# CH32H417MEU6-UHSIF-Top-R0.net
KiCad netlist of a schematic drawn in Altium Designer
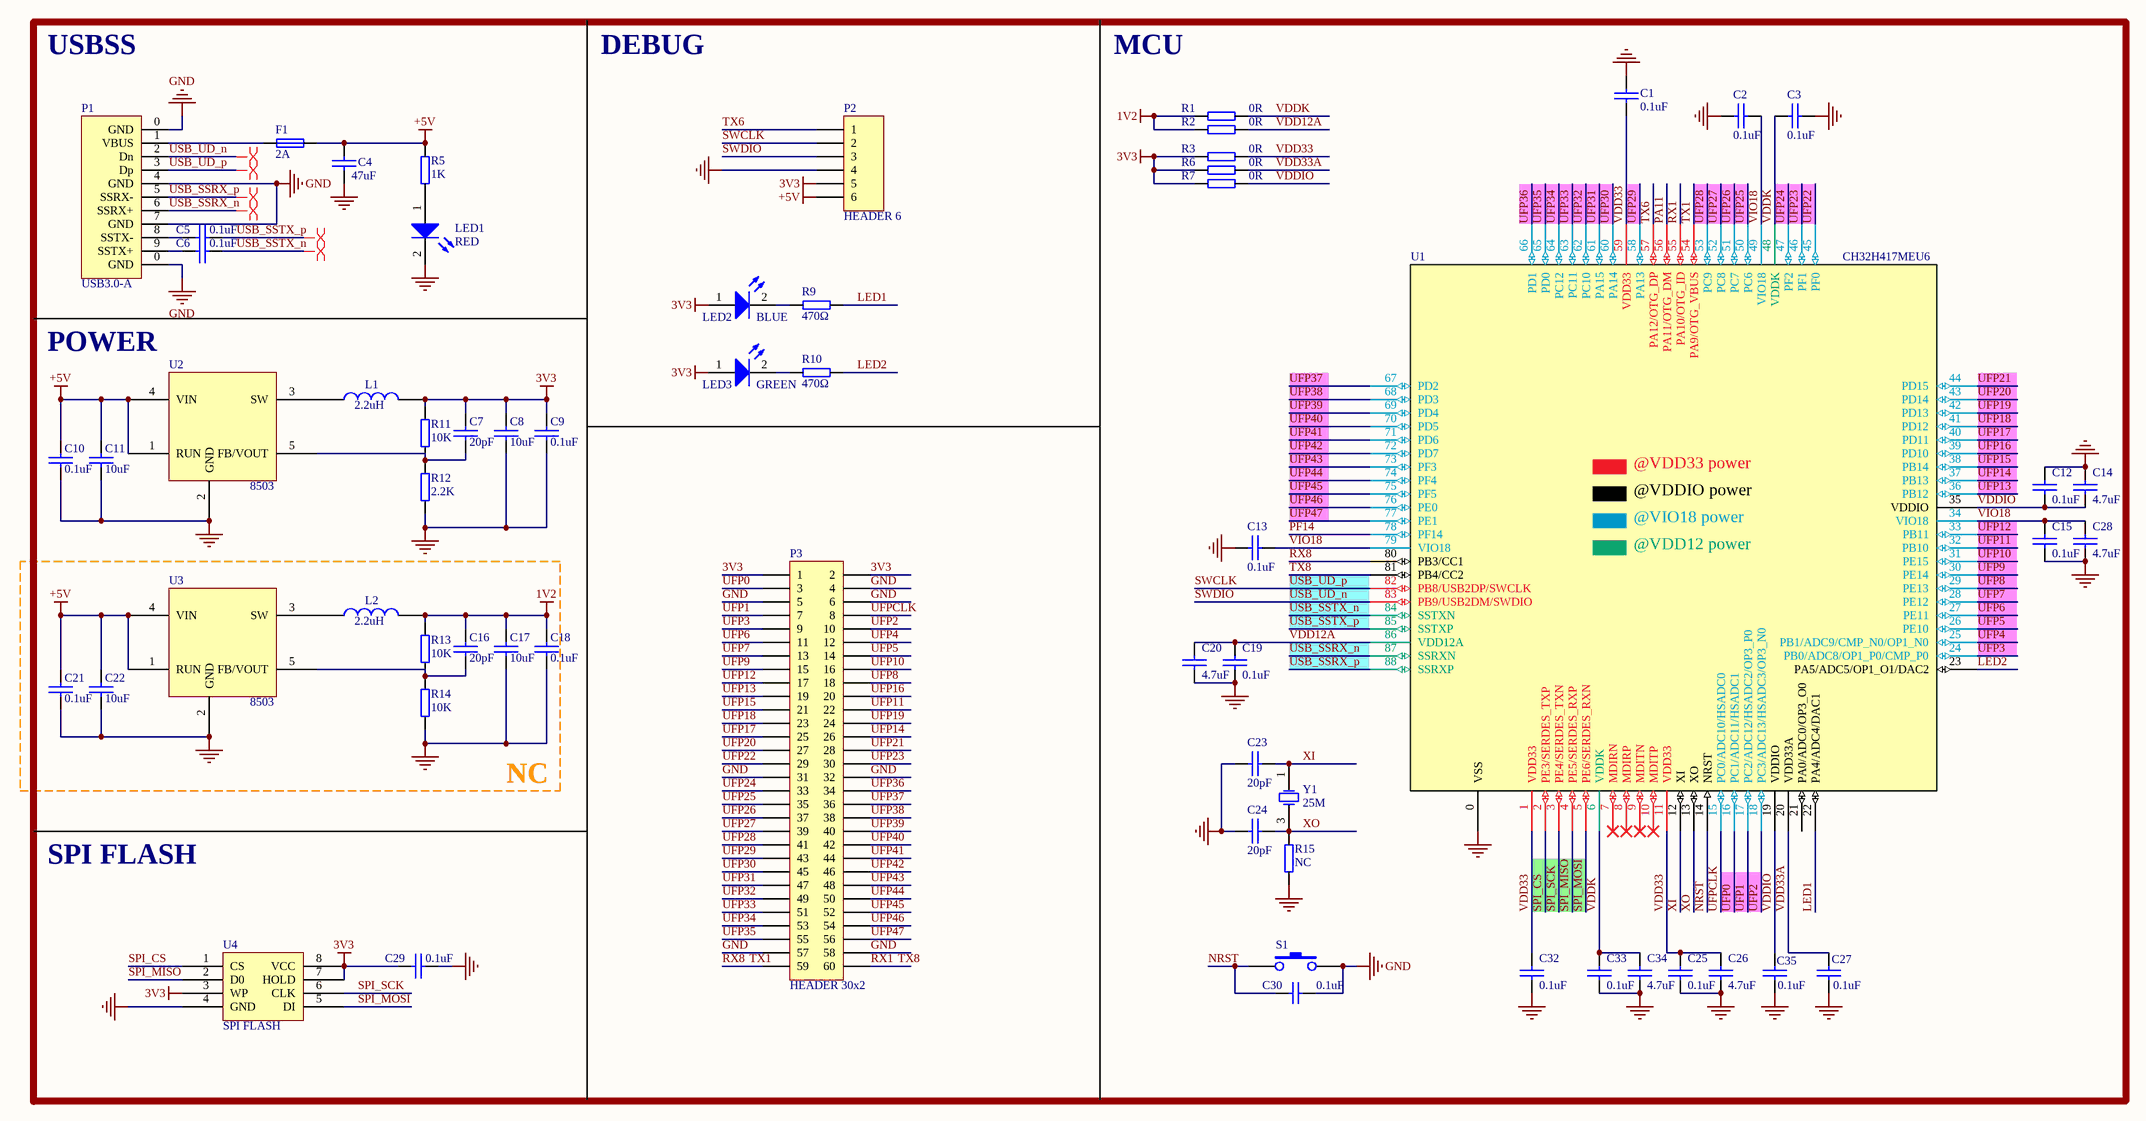
[diagram p0: CH32H417MEU6-UHSIF-Top-R0.SchDoc]

(export (version "E")
  (design (tool "Eeschema 10.0.6"))
  (components
    (comp (ref "C1")
      (value "0.1uF")
      (footprint "0402_C")
      (description "Capacitor")
      (libsource (lib "wch_sch_others") (part "CAP"))
    )
    (comp (ref "C2")
      (value "0.1uF")
      (footprint "0402_C")
      (description "Capacitor")
      (libsource (lib "wch_sch_others") (part "CAP"))
    )
    (comp (ref "C3")
      (value "0.1uF")
      (footprint "0402_C")
      (description "Capacitor")
      (libsource (lib "wch_sch_others") (part "CAP"))
    )
    (comp (ref "C4")
      (value "47uF")
      (footprint "3528_C")
      (description "Capacitor")
      (libsource (lib "wch_sch_others") (part "CAP"))
    )
    (comp (ref "C5")
      (value "0.1uF")
      (footprint "0402_C")
      (description "Capacitor")
      (libsource (lib "wch_sch_others") (part "CAP"))
    )
    (comp (ref "C6")
      (value "0.1uF")
      (footprint "0402_C")
      (description "Capacitor")
      (libsource (lib "wch_sch_others") (part "CAP"))
    )
    (comp (ref "C7")
      (value "20pF")
      (footprint "0402_C")
      (description "Capacitor")
      (libsource (lib "*") (part "CAP"))
    )
    (comp (ref "C8")
      (value "10uF")
      (footprint "0603_C")
      (description "Capacitor")
      (libsource (lib "") (part "CAP_1"))
    )
    (comp (ref "C9")
      (value "0.1uF")
      (footprint "0402_C")
      (description "Capacitor")
      (libsource (lib "*") (part "CAP"))
    )
    (comp (ref "C10")
      (value "0.1uF")
      (footprint "0402_C")
      (description "Capacitor")
      (libsource (lib "*") (part "CAP"))
    )
    (comp (ref "C11")
      (value "10uF")
      (footprint "0603_C")
      (description "Capacitor")
      (libsource (lib "") (part "CAP_1"))
    )
    (comp (ref "C12")
      (value "0.1uF")
      (footprint "0402_C")
      (description "Capacitor")
      (libsource (lib "wch_sch_others") (part "CAP"))
    )
    (comp (ref "C13")
      (value "0.1uF")
      (footprint "0402_C")
      (description "Capacitor")
      (libsource (lib "wch_sch_others") (part "CAP"))
    )
    (comp (ref "C14")
      (value "4.7uF")
      (footprint "0402_C")
      (description "Capacitor")
      (libsource (lib "wch_sch_others") (part "CAP"))
    )
    (comp (ref "C15")
      (value "0.1uF")
      (footprint "0402_C")
      (description "Capacitor")
      (libsource (lib "wch_sch_others") (part "CAP"))
    )
    (comp (ref "C16")
      (value "20pF")
      (footprint "0402_C")
      (description "Capacitor")
      (libsource (lib "*") (part "CAP"))
    )
    (comp (ref "C17")
      (value "10uF")
      (footprint "0603_C")
      (description "Capacitor")
      (libsource (lib "") (part "CAP_1"))
    )
    (comp (ref "C18")
      (value "0.1uF")
      (footprint "0402_C")
      (description "Capacitor")
      (libsource (lib "*") (part "CAP"))
    )
    (comp (ref "C19")
      (value "0.1uF")
      (footprint "0402_C")
      (description "Capacitor")
      (libsource (lib "wch_sch_others") (part "CAP"))
    )
    (comp (ref "C20")
      (value "4.7uF")
      (footprint "0402_C")
      (description "Capacitor")
      (libsource (lib "wch_sch_others") (part "CAP"))
    )
    (comp (ref "C21")
      (value "0.1uF")
      (footprint "0402_C")
      (description "Capacitor")
      (libsource (lib "*") (part "CAP"))
    )
    (comp (ref "C22")
      (value "10uF")
      (footprint "0603_C")
      (description "Capacitor")
      (libsource (lib "") (part "CAP_1"))
    )
    (comp (ref "C23")
      (value "20pF")
      (footprint "0402_C")
      (description "Capacitor")
      (libsource (lib "wch_sch_others") (part "CAP"))
    )
    (comp (ref "C24")
      (value "20pF")
      (footprint "0402_C")
      (description "Capacitor")
      (libsource (lib "wch_sch_others") (part "CAP"))
    )
    (comp (ref "C25")
      (value "0.1uF")
      (footprint "0402_C")
      (description "Capacitor")
      (libsource (lib "wch_sch_others") (part "CAP"))
    )
    (comp (ref "C26")
      (value "4.7uF")
      (footprint "0402_C")
      (description "Capacitor")
      (libsource (lib "wch_sch_others") (part "CAP"))
    )
    (comp (ref "C27")
      (value "0.1uF")
      (footprint "0402_C")
      (description "Capacitor")
      (libsource (lib "wch_sch_others") (part "CAP"))
    )
    (comp (ref "C28")
      (value "4.7uF")
      (footprint "0402_C")
      (description "Capacitor")
      (libsource (lib "wch_sch_others") (part "CAP"))
    )
    (comp (ref "C29")
      (value "0.1uF")
      (footprint "0402_C")
      (description "Capacitor")
      (libsource (lib "wch_sch_others") (part "CAP"))
    )
    (comp (ref "C30")
      (value "0.1uF")
      (footprint "0402_C")
      (description "Capacitor")
      (libsource (lib "Miscellaneous Devices") (part "Cap"))
    )
    (comp (ref "C32")
      (value "0.1uF")
      (footprint "0402_C")
      (description "Capacitor")
      (libsource (lib "wch_sch_others") (part "CAP"))
    )
    (comp (ref "C33")
      (value "0.1uF")
      (footprint "0402_C")
      (description "Capacitor")
      (libsource (lib "wch_sch_others") (part "CAP"))
    )
    (comp (ref "C34")
      (value "4.7uF")
      (footprint "0402_C")
      (description "Capacitor")
      (libsource (lib "wch_sch_others") (part "CAP"))
    )
    (comp (ref "C35")
      (value "0.1uF")
      (footprint "0402_C")
      (description "Capacitor")
      (libsource (lib "wch_sch_others") (part "CAP"))
    )
    (comp (ref "F1")
      (value "2A")
      (footprint "0805")
      (description "Fuse")
      (libsource (lib "wch_sch_others") (part "FUSE1"))
    )
    (comp (ref "L1") (value "2.2uH") (footprint "CD32") (libsource (lib "*") (part "INDUCTOR")))
    (comp (ref "L2") (value "2.2uH") (footprint "CD32") (libsource (lib "*") (part "INDUCTOR")))
    (comp (ref "LED1")
      (value "RED")
      (footprint "MYPCB:0603+")
      (description "Typical INFRARED GaAs LED")
      (libsource (lib "wch_sch_others") (part "LED"))
    )
    (comp (ref "LED2")
      (value "BLUE")
      (footprint "MYPCB:0603+")
      (description "Typical INFRARED GaAs LED")
      (libsource (lib "wch_sch_others") (part "LED"))
    )
    (comp (ref "LED3")
      (value "GREEN")
      (footprint "MYPCB:0603+")
      (description "Typical INFRARED GaAs LED")
      (libsource (lib "wch_sch_others") (part "LED"))
    )
    (comp (ref "P1")
      (value "USB3.0-A")
      (footprint "USB3.0-A-Receptacle")
      (libsource (lib "wch_sch_others") (part "USB3.0-A"))
    )
    (comp (ref "P2")
      (value "HEADER 6")
      (footprint "SIP6-2.54mm")
      (description "Header, 6-Pin")
      (libsource (lib "wch_sch_others") (part "HEADER 6"))
    )
    (comp (ref "P3")
      (value "HEADER 30x2")
      (footprint "MYPCB:BTB-60P-P0.5-FR")
      (description "Header, 30-Pin, Dual row")
      (libsource (lib "wch_sch_others") (part "HEADER 30x2"))
    )
    (comp (ref "R1") (value "0R") (footprint "0603") (libsource (lib "wch_sch_others") (part "RES")))
    (comp (ref "R2") (value "0R") (footprint "0603") (libsource (lib "wch_sch_others") (part "RES")))
    (comp (ref "R3") (value "0R") (footprint "0603") (libsource (lib "wch_sch_others") (part "RES")))
    (comp (ref "R5") (value "1K") (footprint "0402") (libsource (lib "wch_sch_others") (part "RES")))
    (comp (ref "R6") (value "0R") (footprint "0603") (libsource (lib "wch_sch_others") (part "RES")))
    (comp (ref "R7") (value "0R") (footprint "0603") (libsource (lib "wch_sch_others") (part "RES")))
    (comp (ref "R9") (value "470Ω") (footprint "0402") (libsource (lib "wch_sch_others") (part "RES")))
    (comp (ref "R10") (value "470Ω") (footprint "0402") (libsource (lib "wch_sch_others") (part "RES")))
    (comp (ref "R11") (value "10K") (footprint "0402") (libsource (lib "*") (part "R")))
    (comp (ref "R12") (value "2.2K") (footprint "0402") (libsource (lib "*") (part "R")))
    (comp (ref "R13") (value "10K") (footprint "0402") (libsource (lib "*") (part "R")))
    (comp (ref "R14") (value "10K") (footprint "0402") (libsource (lib "*") (part "R")))
    (comp (ref "R15") (value "NC") (footprint "0402") (libsource (lib "*") (part "RES")))
    (comp (ref "S1") (value "~") (footprint "贴片按键") (libsource (lib "wch_sch_others") (part "KEY1")))
    (comp (ref "U1")
      (value "CH32H417MEU6")
      (footprint "QFN88_10X10")
      (description "RISC-V FPU HD-MCU, 384MHz, USB3.0 & PD, 100M Ethernet, DVP, SDMMC, QSPI, OPA, ADC, DAC")
      (libsource (lib "DHXXXSCH") (part "CH32H417MEU6"))
    )
    (comp (ref "U2") (value "8503") (footprint "SOT-23-5") (libsource (lib "*") (part "FP6160")))
    (comp (ref "U3") (value "8503") (footprint "SOT-23-5") (libsource (lib "*") (part "FP6160")))
    (comp (ref "U4")
      (value "SPI FLASH")
      (footprint "SOIC-8_208mil")
      (libsource (lib "wch_sch_others") (part "W25Q64"))
    )
    (comp (ref "Y1")
      (value "25M")
      (footprint "XT3225")
      (description "Crystal Oscillator")
      (fields (field (name "PUBLISHER") "Altium Limited"))
      (libsource (lib "Miscellaneous Devices") (part "XTAL"))
    )
  )
  (nets
    (net (code "1") (name "+5V") (class "Default")
      (node (ref "C10") (pin "2") (pinfunction "2_2") (pintype "passive"))
      (node (ref "C11") (pin "2") (pinfunction "2_2") (pintype "passive"))
      (node (ref "C21") (pin "2") (pinfunction "2_2") (pintype "passive"))
      (node (ref "C22") (pin "2") (pinfunction "2_2") (pintype "passive"))
      (node (ref "C4") (pin "1") (pinfunction "1_1") (pintype "passive"))
      (node (ref "F1") (pin "2") (pintype "passive"))
      (node (ref "P2") (pin "6") (pinfunction "6_6") (pintype "passive"))
      (node (ref "R5") (pin "2") (pintype "passive"))
      (node (ref "U2") (pin "1") (pinfunction "RUN_1") (pintype "passive"))
      (node (ref "U2") (pin "4") (pinfunction "VIN_4") (pintype "passive"))
      (node (ref "U3") (pin "1") (pinfunction "RUN_1") (pintype "passive"))
      (node (ref "U3") (pin "4") (pinfunction "VIN_4") (pintype "passive"))
    )
    (net (code "2") (name "/LED1") (class "Default")
      (node (ref "R9") (pin "1") (pintype "passive"))
      (node (ref "U1") (pin "22") (pinfunction "PA4/ADC4/DAC1_22") (pintype "bidirectional"))
    )
    (net (code "3") (name "/LED2") (class "Default")
      (node (ref "R10") (pin "1") (pintype "passive"))
      (node (ref "U1") (pin "23") (pinfunction "PA5/ADC5/OP1_O1/DAC2_23") (pintype "bidirectional"))
    )
    (net (code "4") (name "/NRST") (class "Default")
      (node (ref "C30") (pin "2") (pinfunction "2_2") (pintype "passive"))
      (node (ref "S1") (pin "1") (pinfunction "1_1") (pintype "passive"))
      (node (ref "U1") (pin "14") (pinfunction "NRST_14") (pintype "input"))
    )
    (net (code "5") (name "/PA11") (class "Default")
      (node (ref "U1") (pin "56") (pinfunction "PA11/OTG_DM_56") (pintype "bidirectional"))
    )
    (net (code "6") (name "/PF14") (class "Default")
      (node (ref "U1") (pin "78") (pinfunction "PF14_78") (pintype "bidirectional"))
    )
    (net (code "7") (name "/RX1") (class "Default")
      (node (ref "P3") (pin "60") (pinfunction "60_60") (pintype "passive"))
      (node (ref "U1") (pin "55") (pinfunction "PA10/OTG_ID_55") (pintype "bidirectional"))
      (node (ref "U1") (pin "81") (pinfunction "PB4/CC2_81") (pintype "bidirectional"))
    )
    (net (code "8") (name "/RX8") (class "Default")
      (node (ref "P3") (pin "59") (pinfunction "59_59") (pintype "passive"))
      (node (ref "U1") (pin "54") (pinfunction "PA9/OTG_VBUS_54") (pintype "bidirectional"))
      (node (ref "U1") (pin "80") (pinfunction "PB3/CC1_80") (pintype "bidirectional"))
    )
    (net (code "9") (name "/SPI_CS") (class "Default")
      (node (ref "U1") (pin "2") (pinfunction "PE3/SERDES_TXP_2") (pintype "bidirectional"))
      (node (ref "U4") (pin "1") (pinfunction "CS_1") (pintype "passive"))
    )
    (net (code "10") (name "/SPI_MISO") (class "Default")
      (node (ref "U1") (pin "4") (pinfunction "PE5/SERDES_RXP_4") (pintype "bidirectional"))
      (node (ref "U4") (pin "2") (pinfunction "D0_2") (pintype "passive"))
    )
    (net (code "11") (name "/SPI_MOSI") (class "Default")
      (node (ref "U1") (pin "5") (pinfunction "PE6/SERDES_RXN_5") (pintype "bidirectional"))
      (node (ref "U4") (pin "5") (pinfunction "DI_5") (pintype "passive"))
    )
    (net (code "12") (name "/SPI_SCK") (class "Default")
      (node (ref "U1") (pin "3") (pinfunction "PE4/SERDES_TXN_3") (pintype "bidirectional"))
      (node (ref "U4") (pin "6") (pinfunction "CLK_6") (pintype "passive"))
    )
    (net (code "13") (name "/SWCLK") (class "Default")
      (node (ref "P1") (pin "3") (pinfunction "Dp_3") (pintype "passive"))
      (node (ref "P2") (pin "2") (pinfunction "2_2") (pintype "passive"))
      (node (ref "U1") (pin "82") (pinfunction "PB8/USB2DP/SWCLK_82") (pintype "bidirectional"))
    )
    (net (code "14") (name "/SWDIO") (class "Default")
      (node (ref "P1") (pin "2") (pinfunction "Dn_2") (pintype "passive"))
      (node (ref "P2") (pin "3") (pinfunction "3_3") (pintype "passive"))
      (node (ref "U1") (pin "83") (pinfunction "PB9/USB2DM/SWDIO_83") (pintype "bidirectional"))
    )
    (net (code "15") (name "/TX6") (class "Default")
      (node (ref "P2") (pin "1") (pinfunction "1_1") (pintype "passive"))
      (node (ref "U1") (pin "57") (pinfunction "PA12/OTG_DP_57") (pintype "bidirectional"))
    )
    (net (code "16") (name "/UFP0") (class "Default")
      (node (ref "P3") (pin "3") (pinfunction "3_3") (pintype "passive"))
      (node (ref "U1") (pin "16") (pinfunction "PC1/ADC11/HSADC1_16") (pintype "bidirectional"))
    )
    (net (code "17") (name "/UFP1") (class "Default")
      (node (ref "P3") (pin "7") (pinfunction "7_7") (pintype "passive"))
      (node (ref "U1") (pin "17") (pinfunction "PC2/ADC12/HSADC2/OP3_P0_17") (pintype "bidirectional"))
    )
    (net (code "18") (name "/UFP2") (class "Default")
      (node (ref "P3") (pin "10") (pinfunction "10_10") (pintype "passive"))
      (node (ref "U1") (pin "18") (pinfunction "PC3/ADC13/HSADC3/OP3_N0_18") (pintype "bidirectional"))
    )
    (net (code "19") (name "/UFP3") (class "Default")
      (node (ref "P3") (pin "9") (pinfunction "9_9") (pintype "passive"))
      (node (ref "U1") (pin "24") (pinfunction "PB0/ADC8/OP1_P0/CMP_P0_24") (pintype "bidirectional"))
    )
    (net (code "20") (name "/UFP4") (class "Default")
      (node (ref "P3") (pin "12") (pinfunction "12_12") (pintype "passive"))
      (node (ref "U1") (pin "25") (pinfunction "PB1/ADC9/CMP_N0/OP1_N0_25") (pintype "bidirectional"))
    )
    (net (code "21") (name "/UFP5") (class "Default")
      (node (ref "P3") (pin "14") (pinfunction "14_14") (pintype "passive"))
      (node (ref "U1") (pin "26") (pinfunction "PE10_26") (pintype "bidirectional"))
    )
    (net (code "22") (name "/UFP6") (class "Default")
      (node (ref "P3") (pin "11") (pinfunction "11_11") (pintype "passive"))
      (node (ref "U1") (pin "27") (pinfunction "PE11_27") (pintype "bidirectional"))
    )
    (net (code "23") (name "/UFP7") (class "Default")
      (node (ref "P3") (pin "13") (pinfunction "13_13") (pintype "passive"))
      (node (ref "U1") (pin "28") (pinfunction "PE12_28") (pintype "bidirectional"))
    )
    (net (code "24") (name "/UFP8") (class "Default")
      (node (ref "P3") (pin "18") (pinfunction "18_18") (pintype "passive"))
      (node (ref "U1") (pin "29") (pinfunction "PE13_29") (pintype "bidirectional"))
    )
    (net (code "25") (name "/UFP9") (class "Default")
      (node (ref "P3") (pin "15") (pinfunction "15_15") (pintype "passive"))
      (node (ref "U1") (pin "30") (pinfunction "PE14_30") (pintype "bidirectional"))
    )
    (net (code "26") (name "/UFP10") (class "Default")
      (node (ref "P3") (pin "16") (pinfunction "16_16") (pintype "passive"))
      (node (ref "U1") (pin "31") (pinfunction "PE15_31") (pintype "bidirectional"))
    )
    (net (code "27") (name "/UFP11") (class "Default")
      (node (ref "P3") (pin "22") (pinfunction "22_22") (pintype "passive"))
      (node (ref "U1") (pin "32") (pinfunction "PB10_32") (pintype "bidirectional"))
    )
    (net (code "28") (name "/UFP12") (class "Default")
      (node (ref "P3") (pin "17") (pinfunction "17_17") (pintype "passive"))
      (node (ref "U1") (pin "33") (pinfunction "PB11_33") (pintype "bidirectional"))
    )
    (net (code "29") (name "/UFP13") (class "Default")
      (node (ref "P3") (pin "19") (pinfunction "19_19") (pintype "passive"))
      (node (ref "U1") (pin "36") (pinfunction "PB12_36") (pintype "bidirectional"))
    )
    (net (code "30") (name "/UFP14") (class "Default")
      (node (ref "P3") (pin "26") (pinfunction "26_26") (pintype "passive"))
      (node (ref "U1") (pin "37") (pinfunction "PB13_37") (pintype "bidirectional"))
    )
    (net (code "31") (name "/UFP15") (class "Default")
      (node (ref "P3") (pin "21") (pinfunction "21_21") (pintype "passive"))
      (node (ref "U1") (pin "38") (pinfunction "PB14_38") (pintype "bidirectional"))
    )
    (net (code "32") (name "/UFP16") (class "Default")
      (node (ref "P3") (pin "20") (pinfunction "20_20") (pintype "passive"))
      (node (ref "U1") (pin "39") (pinfunction "PD10_39") (pintype "bidirectional"))
    )
    (net (code "33") (name "/UFP17") (class "Default")
      (node (ref "P3") (pin "25") (pinfunction "25_25") (pintype "passive"))
      (node (ref "U1") (pin "40") (pinfunction "PD11_40") (pintype "bidirectional"))
    )
    (net (code "34") (name "/UFP18") (class "Default")
      (node (ref "P3") (pin "23") (pinfunction "23_23") (pintype "passive"))
      (node (ref "U1") (pin "41") (pinfunction "PD12_41") (pintype "bidirectional"))
    )
    (net (code "35") (name "/UFP19") (class "Default")
      (node (ref "P3") (pin "24") (pinfunction "24_24") (pintype "passive"))
      (node (ref "U1") (pin "42") (pinfunction "PD13_42") (pintype "bidirectional"))
    )
    (net (code "36") (name "/UFP20") (class "Default")
      (node (ref "P3") (pin "27") (pinfunction "27_27") (pintype "passive"))
      (node (ref "U1") (pin "43") (pinfunction "PD14_43") (pintype "bidirectional"))
    )
    (net (code "37") (name "/UFP21") (class "Default")
      (node (ref "P3") (pin "28") (pinfunction "28_28") (pintype "passive"))
      (node (ref "U1") (pin "44") (pinfunction "PD15_44") (pintype "bidirectional"))
    )
    (net (code "38") (name "/UFP22") (class "Default")
      (node (ref "P3") (pin "29") (pinfunction "29_29") (pintype "passive"))
      (node (ref "U1") (pin "45") (pinfunction "PF0_45") (pintype "bidirectional"))
    )
    (net (code "39") (name "/UFP23") (class "Default")
      (node (ref "P3") (pin "30") (pinfunction "30_30") (pintype "passive"))
      (node (ref "U1") (pin "46") (pinfunction "PF1_46") (pintype "bidirectional"))
    )
    (net (code "40") (name "/UFP24") (class "Default")
      (node (ref "P3") (pin "33") (pinfunction "33_33") (pintype "passive"))
      (node (ref "U1") (pin "47") (pinfunction "PF2_47") (pintype "bidirectional"))
    )
    (net (code "41") (name "/UFP25") (class "Default")
      (node (ref "P3") (pin "35") (pinfunction "35_35") (pintype "passive"))
      (node (ref "U1") (pin "50") (pinfunction "PC6_50") (pintype "bidirectional"))
    )
    (net (code "42") (name "/UFP26") (class "Default")
      (node (ref "P3") (pin "37") (pinfunction "37_37") (pintype "passive"))
      (node (ref "U1") (pin "51") (pinfunction "PC7_51") (pintype "bidirectional"))
    )
    (net (code "43") (name "/UFP27") (class "Default")
      (node (ref "P3") (pin "39") (pinfunction "39_39") (pintype "passive"))
      (node (ref "U1") (pin "52") (pinfunction "PC8_52") (pintype "bidirectional"))
    )
    (net (code "44") (name "/UFP28") (class "Default")
      (node (ref "P3") (pin "41") (pinfunction "41_41") (pintype "passive"))
      (node (ref "U1") (pin "53") (pinfunction "PC9_53") (pintype "bidirectional"))
    )
    (net (code "45") (name "/UFP29") (class "Default")
      (node (ref "P3") (pin "43") (pinfunction "43_43") (pintype "passive"))
      (node (ref "U1") (pin "58") (pinfunction "PA13_58") (pintype "bidirectional"))
    )
    (net (code "46") (name "/UFP30") (class "Default")
      (node (ref "P3") (pin "45") (pinfunction "45_45") (pintype "passive"))
      (node (ref "U1") (pin "60") (pinfunction "PA14_60") (pintype "bidirectional"))
    )
    (net (code "47") (name "/UFP31") (class "Default")
      (node (ref "P3") (pin "47") (pinfunction "47_47") (pintype "passive"))
      (node (ref "U1") (pin "61") (pinfunction "PA15_61") (pintype "bidirectional"))
    )
    (net (code "48") (name "/UFP32") (class "Default")
      (node (ref "P3") (pin "49") (pinfunction "49_49") (pintype "passive"))
      (node (ref "U1") (pin "62") (pinfunction "PC10_62") (pintype "bidirectional"))
    )
    (net (code "49") (name "/UFP33") (class "Default")
      (node (ref "P3") (pin "51") (pinfunction "51_51") (pintype "passive"))
      (node (ref "U1") (pin "63") (pinfunction "PC11_63") (pintype "bidirectional"))
    )
    (net (code "50") (name "/UFP34") (class "Default")
      (node (ref "P3") (pin "53") (pinfunction "53_53") (pintype "passive"))
      (node (ref "U1") (pin "64") (pinfunction "PC12_64") (pintype "bidirectional"))
    )
    (net (code "51") (name "/UFP35") (class "Default")
      (node (ref "P3") (pin "55") (pinfunction "55_55") (pintype "passive"))
      (node (ref "U1") (pin "65") (pinfunction "PD0_65") (pintype "bidirectional"))
    )
    (net (code "52") (name "/UFP36") (class "Default")
      (node (ref "P3") (pin "34") (pinfunction "34_34") (pintype "passive"))
      (node (ref "U1") (pin "66") (pinfunction "PD1_66") (pintype "bidirectional"))
    )
    (net (code "53") (name "/UFP37") (class "Default")
      (node (ref "P3") (pin "36") (pinfunction "36_36") (pintype "passive"))
      (node (ref "U1") (pin "67") (pinfunction "PD2_67") (pintype "bidirectional"))
    )
    (net (code "54") (name "/UFP38") (class "Default")
      (node (ref "P3") (pin "38") (pinfunction "38_38") (pintype "passive"))
      (node (ref "U1") (pin "68") (pinfunction "PD3_68") (pintype "bidirectional"))
    )
    (net (code "55") (name "/UFP39") (class "Default")
      (node (ref "P3") (pin "40") (pinfunction "40_40") (pintype "passive"))
      (node (ref "U1") (pin "69") (pinfunction "PD4_69") (pintype "bidirectional"))
    )
    (net (code "56") (name "/UFP40") (class "Default")
      (node (ref "P3") (pin "42") (pinfunction "42_42") (pintype "passive"))
      (node (ref "U1") (pin "70") (pinfunction "PD5_70") (pintype "bidirectional"))
    )
    (net (code "57") (name "/UFP41") (class "Default")
      (node (ref "P3") (pin "44") (pinfunction "44_44") (pintype "passive"))
      (node (ref "U1") (pin "71") (pinfunction "PD6_71") (pintype "bidirectional"))
    )
    (net (code "58") (name "/UFP42") (class "Default")
      (node (ref "P3") (pin "46") (pinfunction "46_46") (pintype "passive"))
      (node (ref "U1") (pin "72") (pinfunction "PD7_72") (pintype "bidirectional"))
    )
    (net (code "59") (name "/UFP43") (class "Default")
      (node (ref "P3") (pin "48") (pinfunction "48_48") (pintype "passive"))
      (node (ref "U1") (pin "73") (pinfunction "PF3_73") (pintype "bidirectional"))
    )
    (net (code "60") (name "/UFP44") (class "Default")
      (node (ref "P3") (pin "50") (pinfunction "50_50") (pintype "passive"))
      (node (ref "U1") (pin "74") (pinfunction "PF4_74") (pintype "bidirectional"))
    )
    (net (code "61") (name "/UFP45") (class "Default")
      (node (ref "P3") (pin "52") (pinfunction "52_52") (pintype "passive"))
      (node (ref "U1") (pin "75") (pinfunction "PF5_75") (pintype "bidirectional"))
    )
    (net (code "62") (name "/UFP46") (class "Default")
      (node (ref "P3") (pin "54") (pinfunction "54_54") (pintype "passive"))
      (node (ref "U1") (pin "76") (pinfunction "PE0_76") (pintype "bidirectional"))
    )
    (net (code "63") (name "/UFP47") (class "Default")
      (node (ref "P3") (pin "56") (pinfunction "56_56") (pintype "passive"))
      (node (ref "U1") (pin "77") (pinfunction "PE1_77") (pintype "bidirectional"))
    )
    (net (code "64") (name "/UFPCLK") (class "Default")
      (node (ref "P3") (pin "8") (pinfunction "8_8") (pintype "passive"))
      (node (ref "U1") (pin "15") (pinfunction "PC0/ADC10/HSADC0_15") (pintype "bidirectional"))
    )
    (net (code "65") (name "/USB_SSRX_n") (class "Default")
      (node (ref "P1") (pin "6") (pinfunction "SSRX+_6") (pintype "passive"))
      (node (ref "U1") (pin "87") (pinfunction "SSRXN_87") (pintype "bidirectional"))
    )
    (net (code "66") (name "/USB_SSRX_p") (class "Default")
      (node (ref "P1") (pin "5") (pinfunction "SSRX-_5") (pintype "passive"))
      (node (ref "U1") (pin "88") (pinfunction "SSRXP_88") (pintype "bidirectional"))
    )
    (net (code "67") (name "/USB_SSTX_n") (class "Default")
      (node (ref "C6") (pin "1") (pinfunction "1_1") (pintype "passive"))
      (node (ref "U1") (pin "84") (pinfunction "SSTXN_84") (pintype "bidirectional"))
    )
    (net (code "68") (name "/USB_SSTX_p") (class "Default")
      (node (ref "C5") (pin "1") (pinfunction "1_1") (pintype "passive"))
      (node (ref "U1") (pin "85") (pinfunction "SSTXP_85") (pintype "bidirectional"))
    )
    (net (code "69") (name "/VDD12A") (class "Default")
      (node (ref "C19") (pin "2") (pinfunction "2_2") (pintype "passive"))
      (node (ref "C20") (pin "2") (pinfunction "2_2") (pintype "passive"))
      (node (ref "R2") (pin "1") (pintype "passive"))
      (node (ref "U1") (pin "86") (pinfunction "VDD12A_86") (pintype "power_in"))
    )
    (net (code "70") (name "/VDD33") (class "Default")
      (node (ref "C1") (pin "1") (pinfunction "1_1") (pintype "passive"))
      (node (ref "C25") (pin "2") (pinfunction "2_2") (pintype "passive"))
      (node (ref "C26") (pin "2") (pinfunction "2_2") (pintype "passive"))
      (node (ref "C32") (pin "2") (pinfunction "2_2") (pintype "passive"))
      (node (ref "R3") (pin "1") (pintype "passive"))
      (node (ref "U1") (pin "1") (pinfunction "VDD33_1") (pintype "power_in"))
      (node (ref "U1") (pin "11") (pinfunction "VDD33_11") (pintype "power_in"))
      (node (ref "U1") (pin "59") (pinfunction "VDD33_59") (pintype "power_in"))
    )
    (net (code "71") (name "/VDD33A") (class "Default")
      (node (ref "C27") (pin "2") (pinfunction "2_2") (pintype "passive"))
      (node (ref "R6") (pin "1") (pintype "passive"))
      (node (ref "U1") (pin "20") (pinfunction "VDD33A_20") (pintype "power_in"))
    )
    (net (code "72") (name "/VDDIO") (class "Default")
      (node (ref "C12") (pin "1") (pinfunction "1_1") (pintype "passive"))
      (node (ref "C14") (pin "1") (pinfunction "1_1") (pintype "passive"))
      (node (ref "C35") (pin "2") (pinfunction "2_2") (pintype "passive"))
      (node (ref "R7") (pin "1") (pintype "passive"))
      (node (ref "U1") (pin "19") (pinfunction "VDDIO_19") (pintype "power_in"))
      (node (ref "U1") (pin "35") (pinfunction "VDDIO_35") (pintype "power_in"))
    )
    (net (code "73") (name "/VDDK") (class "Default")
      (node (ref "C3") (pin "2") (pinfunction "2_2") (pintype "passive"))
      (node (ref "C33") (pin "2") (pinfunction "2_2") (pintype "passive"))
      (node (ref "C34") (pin "2") (pinfunction "2_2") (pintype "passive"))
      (node (ref "R1") (pin "1") (pintype "passive"))
      (node (ref "U1") (pin "48") (pinfunction "VDDK_48") (pintype "power_in"))
      (node (ref "U1") (pin "6") (pinfunction "VDDK_6") (pintype "power_in"))
    )
    (net (code "74") (name "/VIO18") (class "Default")
      (node (ref "C13") (pin "1") (pinfunction "1_1") (pintype "passive"))
      (node (ref "C15") (pin "2") (pinfunction "2_2") (pintype "passive"))
      (node (ref "C2") (pin "1") (pinfunction "1_1") (pintype "passive"))
      (node (ref "C28") (pin "2") (pinfunction "2_2") (pintype "passive"))
      (node (ref "U1") (pin "34") (pinfunction "VIO18_34") (pintype "power_in"))
      (node (ref "U1") (pin "49") (pinfunction "VIO18_49") (pintype "power_in"))
      (node (ref "U1") (pin "79") (pinfunction "VIO18_79") (pintype "power_in"))
    )
    (net (code "75") (name "/XI") (class "Default")
      (node (ref "C23") (pin "2") (pinfunction "2_2") (pintype "passive"))
      (node (ref "U1") (pin "12") (pinfunction "XI_12") (pintype "bidirectional"))
      (node (ref "Y1") (pin "1") (pinfunction "OSC1_1") (pintype "passive"))
    )
    (net (code "76") (name "/XO") (class "Default")
      (node (ref "C24") (pin "2") (pinfunction "2_2") (pintype "passive"))
      (node (ref "R15") (pin "2") (pintype "passive"))
      (node (ref "U1") (pin "13") (pinfunction "XO_13") (pintype "bidirectional"))
      (node (ref "Y1") (pin "3") (pinfunction "OSC2_3") (pintype "passive"))
    )
    (net (code "77") (name "1V2") (class "Default")
      (node (ref "C16") (pin "1") (pinfunction "1_1") (pintype "passive"))
      (node (ref "C17") (pin "2") (pinfunction "2_2") (pintype "passive"))
      (node (ref "C18") (pin "2") (pinfunction "2_2") (pintype "passive"))
      (node (ref "L2") (pin "2") (pinfunction "2_2") (pintype "passive"))
      (node (ref "R1") (pin "2") (pintype "passive"))
      (node (ref "R13") (pin "1") (pinfunction "1_1") (pintype "passive"))
      (node (ref "R2") (pin "2") (pintype "passive"))
    )
    (net (code "78") (name "3V3") (class "Default")
      (node (ref "C29") (pin "2") (pinfunction "2_2") (pintype "passive"))
      (node (ref "C7") (pin "1") (pinfunction "1_1") (pintype "passive"))
      (node (ref "C8") (pin "2") (pinfunction "2_2") (pintype "passive"))
      (node (ref "C9") (pin "2") (pinfunction "2_2") (pintype "passive"))
      (node (ref "L1") (pin "2") (pinfunction "2_2") (pintype "passive"))
      (node (ref "LED2") (pin "1") (pinfunction "A_1") (pintype "passive"))
      (node (ref "LED3") (pin "1") (pinfunction "A_1") (pintype "passive"))
      (node (ref "P2") (pin "5") (pinfunction "5_5") (pintype "passive"))
      (node (ref "P3") (pin "1") (pinfunction "1_1") (pintype "passive"))
      (node (ref "P3") (pin "2") (pinfunction "2_2") (pintype "passive"))
      (node (ref "R11") (pin "1") (pinfunction "1_1") (pintype "passive"))
      (node (ref "R3") (pin "2") (pintype "passive"))
      (node (ref "R6") (pin "2") (pintype "passive"))
      (node (ref "R7") (pin "2") (pintype "passive"))
      (node (ref "U4") (pin "3") (pinfunction "WP_3") (pintype "passive"))
      (node (ref "U4") (pin "7") (pinfunction "HOLD_7") (pintype "passive"))
      (node (ref "U4") (pin "8") (pinfunction "VCC_8") (pintype "passive"))
    )
    (net (code "79") (name "GND") (class "Default")
      (node (ref "C1") (pin "2") (pinfunction "2_2") (pintype "passive"))
      (node (ref "C10") (pin "1") (pinfunction "1_1") (pintype "passive"))
      (node (ref "C11") (pin "1") (pinfunction "1_1") (pintype "passive"))
      (node (ref "C12") (pin "2") (pinfunction "2_2") (pintype "passive"))
      (node (ref "C13") (pin "2") (pinfunction "2_2") (pintype "passive"))
      (node (ref "C14") (pin "2") (pinfunction "2_2") (pintype "passive"))
      (node (ref "C15") (pin "1") (pinfunction "1_1") (pintype "passive"))
      (node (ref "C17") (pin "1") (pinfunction "1_1") (pintype "passive"))
      (node (ref "C18") (pin "1") (pinfunction "1_1") (pintype "passive"))
      (node (ref "C19") (pin "1") (pinfunction "1_1") (pintype "passive"))
      (node (ref "C2") (pin "2") (pinfunction "2_2") (pintype "passive"))
      (node (ref "C20") (pin "1") (pinfunction "1_1") (pintype "passive"))
      (node (ref "C21") (pin "1") (pinfunction "1_1") (pintype "passive"))
      (node (ref "C22") (pin "1") (pinfunction "1_1") (pintype "passive"))
      (node (ref "C23") (pin "1") (pinfunction "1_1") (pintype "passive"))
      (node (ref "C24") (pin "1") (pinfunction "1_1") (pintype "passive"))
      (node (ref "C25") (pin "1") (pinfunction "1_1") (pintype "passive"))
      (node (ref "C26") (pin "1") (pinfunction "1_1") (pintype "passive"))
      (node (ref "C27") (pin "1") (pinfunction "1_1") (pintype "passive"))
      (node (ref "C28") (pin "1") (pinfunction "1_1") (pintype "passive"))
      (node (ref "C29") (pin "1") (pinfunction "1_1") (pintype "passive"))
      (node (ref "C3") (pin "1") (pinfunction "1_1") (pintype "passive"))
      (node (ref "C30") (pin "1") (pinfunction "1_1") (pintype "passive"))
      (node (ref "C32") (pin "1") (pinfunction "1_1") (pintype "passive"))
      (node (ref "C33") (pin "1") (pinfunction "1_1") (pintype "passive"))
      (node (ref "C34") (pin "1") (pinfunction "1_1") (pintype "passive"))
      (node (ref "C35") (pin "1") (pinfunction "1_1") (pintype "passive"))
      (node (ref "C4") (pin "2") (pinfunction "2_2") (pintype "passive"))
      (node (ref "C8") (pin "1") (pinfunction "1_1") (pintype "passive"))
      (node (ref "C9") (pin "1") (pinfunction "1_1") (pintype "passive"))
      (node (ref "LED1") (pin "2") (pinfunction "K_2") (pintype "passive"))
      (node (ref "P1") (pin "0") (pinfunction "GND_0") (pintype "passive"))
      (node (ref "P1") (pin "4") (pinfunction "GND_4") (pintype "passive"))
      (node (ref "P1") (pin "7") (pinfunction "GND_7") (pintype "passive"))
      (node (ref "P2") (pin "4") (pinfunction "4_4") (pintype "passive"))
      (node (ref "P3") (pin "31") (pinfunction "31_31") (pintype "passive"))
      (node (ref "P3") (pin "32") (pinfunction "32_32") (pintype "passive"))
      (node (ref "P3") (pin "4") (pinfunction "4_4") (pintype "passive"))
      (node (ref "P3") (pin "5") (pinfunction "5_5") (pintype "passive"))
      (node (ref "P3") (pin "57") (pinfunction "57_57") (pintype "passive"))
      (node (ref "P3") (pin "58") (pinfunction "58_58") (pintype "passive"))
      (node (ref "P3") (pin "6") (pinfunction "6_6") (pintype "passive"))
      (node (ref "R12") (pin "1") (pinfunction "1_1") (pintype "passive"))
      (node (ref "R14") (pin "1") (pinfunction "1_1") (pintype "passive"))
      (node (ref "R15") (pin "1") (pintype "passive"))
      (node (ref "S1") (pin "2") (pinfunction "2_2") (pintype "passive"))
      (node (ref "U1") (pin "0") (pinfunction "VSS_0") (pintype "power_in"))
      (node (ref "U2") (pin "2") (pinfunction "GND_2") (pintype "passive"))
      (node (ref "U3") (pin "2") (pinfunction "GND_2") (pintype "passive"))
      (node (ref "U4") (pin "4") (pinfunction "GND_4") (pintype "passive"))
    )
    (net (code "80") (name "Net-(LED1-A)") (class "Default")
      (node (ref "LED1") (pin "1") (pinfunction "A_1") (pintype "passive"))
      (node (ref "R5") (pin "1") (pintype "passive"))
    )
    (net (code "81") (name "Net-(LED2-K)") (class "Default")
      (node (ref "LED2") (pin "2") (pinfunction "K_2") (pintype "passive"))
      (node (ref "R9") (pin "2") (pintype "passive"))
    )
    (net (code "82") (name "Net-(LED3-K)") (class "Default")
      (node (ref "LED3") (pin "2") (pinfunction "K_2") (pintype "passive"))
      (node (ref "R10") (pin "2") (pintype "passive"))
    )
    (net (code "83") (name "Net-(P1-SSTX+)") (class "Default")
      (node (ref "C6") (pin "2") (pinfunction "2_2") (pintype "passive"))
      (node (ref "P1") (pin "9") (pinfunction "SSTX+_9") (pintype "passive"))
    )
    (net (code "84") (name "Net-(P1-SSTX-)") (class "Default")
      (node (ref "C5") (pin "2") (pinfunction "2_2") (pintype "passive"))
      (node (ref "P1") (pin "8") (pinfunction "SSTX-_8") (pintype "passive"))
    )
    (net (code "85") (name "Net-(P1-VBUS)") (class "Default")
      (node (ref "F1") (pin "1") (pintype "passive"))
      (node (ref "P1") (pin "1") (pinfunction "VBUS_1") (pintype "passive"))
    )
    (net (code "86") (name "Net-(U2-FB{slash}VOUT)") (class "Default")
      (node (ref "C7") (pin "2") (pinfunction "2_2") (pintype "passive"))
      (node (ref "R11") (pin "2") (pinfunction "2_2") (pintype "passive"))
      (node (ref "R12") (pin "2") (pinfunction "2_2") (pintype "passive"))
      (node (ref "U2") (pin "5") (pinfunction "FB/VOUT_5") (pintype "passive"))
    )
    (net (code "87") (name "Net-(U2-SW)") (class "Default")
      (node (ref "L1") (pin "1") (pinfunction "1_1") (pintype "passive"))
      (node (ref "U2") (pin "3") (pinfunction "SW_3") (pintype "passive"))
    )
    (net (code "88") (name "Net-(U3-FB{slash}VOUT)") (class "Default")
      (node (ref "C16") (pin "2") (pinfunction "2_2") (pintype "passive"))
      (node (ref "R13") (pin "2") (pinfunction "2_2") (pintype "passive"))
      (node (ref "R14") (pin "2") (pinfunction "2_2") (pintype "passive"))
      (node (ref "U3") (pin "5") (pinfunction "FB/VOUT_5") (pintype "passive"))
    )
    (net (code "89") (name "Net-(U3-SW)") (class "Default")
      (node (ref "L2") (pin "1") (pinfunction "1_1") (pintype "passive"))
      (node (ref "U3") (pin "3") (pinfunction "SW_3") (pintype "passive"))
    )
    (net (code "90") (name "unconnected-(U1-MDIRN-Pad7)") (class "Default")
      (node (ref "U1") (pin "7") (pinfunction "MDIRN_7") (pintype "bidirectional+no_connect"))
    )
    (net (code "91") (name "unconnected-(U1-MDIRP-Pad8)") (class "Default")
      (node (ref "U1") (pin "8") (pinfunction "MDIRP_8") (pintype "bidirectional+no_connect"))
    )
    (net (code "92") (name "unconnected-(U1-MDITN-Pad9)") (class "Default")
      (node (ref "U1") (pin "9") (pinfunction "MDITN_9") (pintype "bidirectional+no_connect"))
    )
    (net (code "93") (name "unconnected-(U1-MDITP-Pad10)") (class "Default")
      (node (ref "U1") (pin "10") (pinfunction "MDITP_10") (pintype "bidirectional+no_connect"))
    )
    (net (code "94") (name "unconnected-(U1-PA0{slash}ADC0{slash}OP3_O0-Pad21)") (class "Default")
      (node (ref "U1") (pin "21") (pinfunction "PA0/ADC0/OP3_O0_21") (pintype "bidirectional"))
    )
  )
)
